# schema.net
KiCad netlist of a schematic drawn in EAGLE
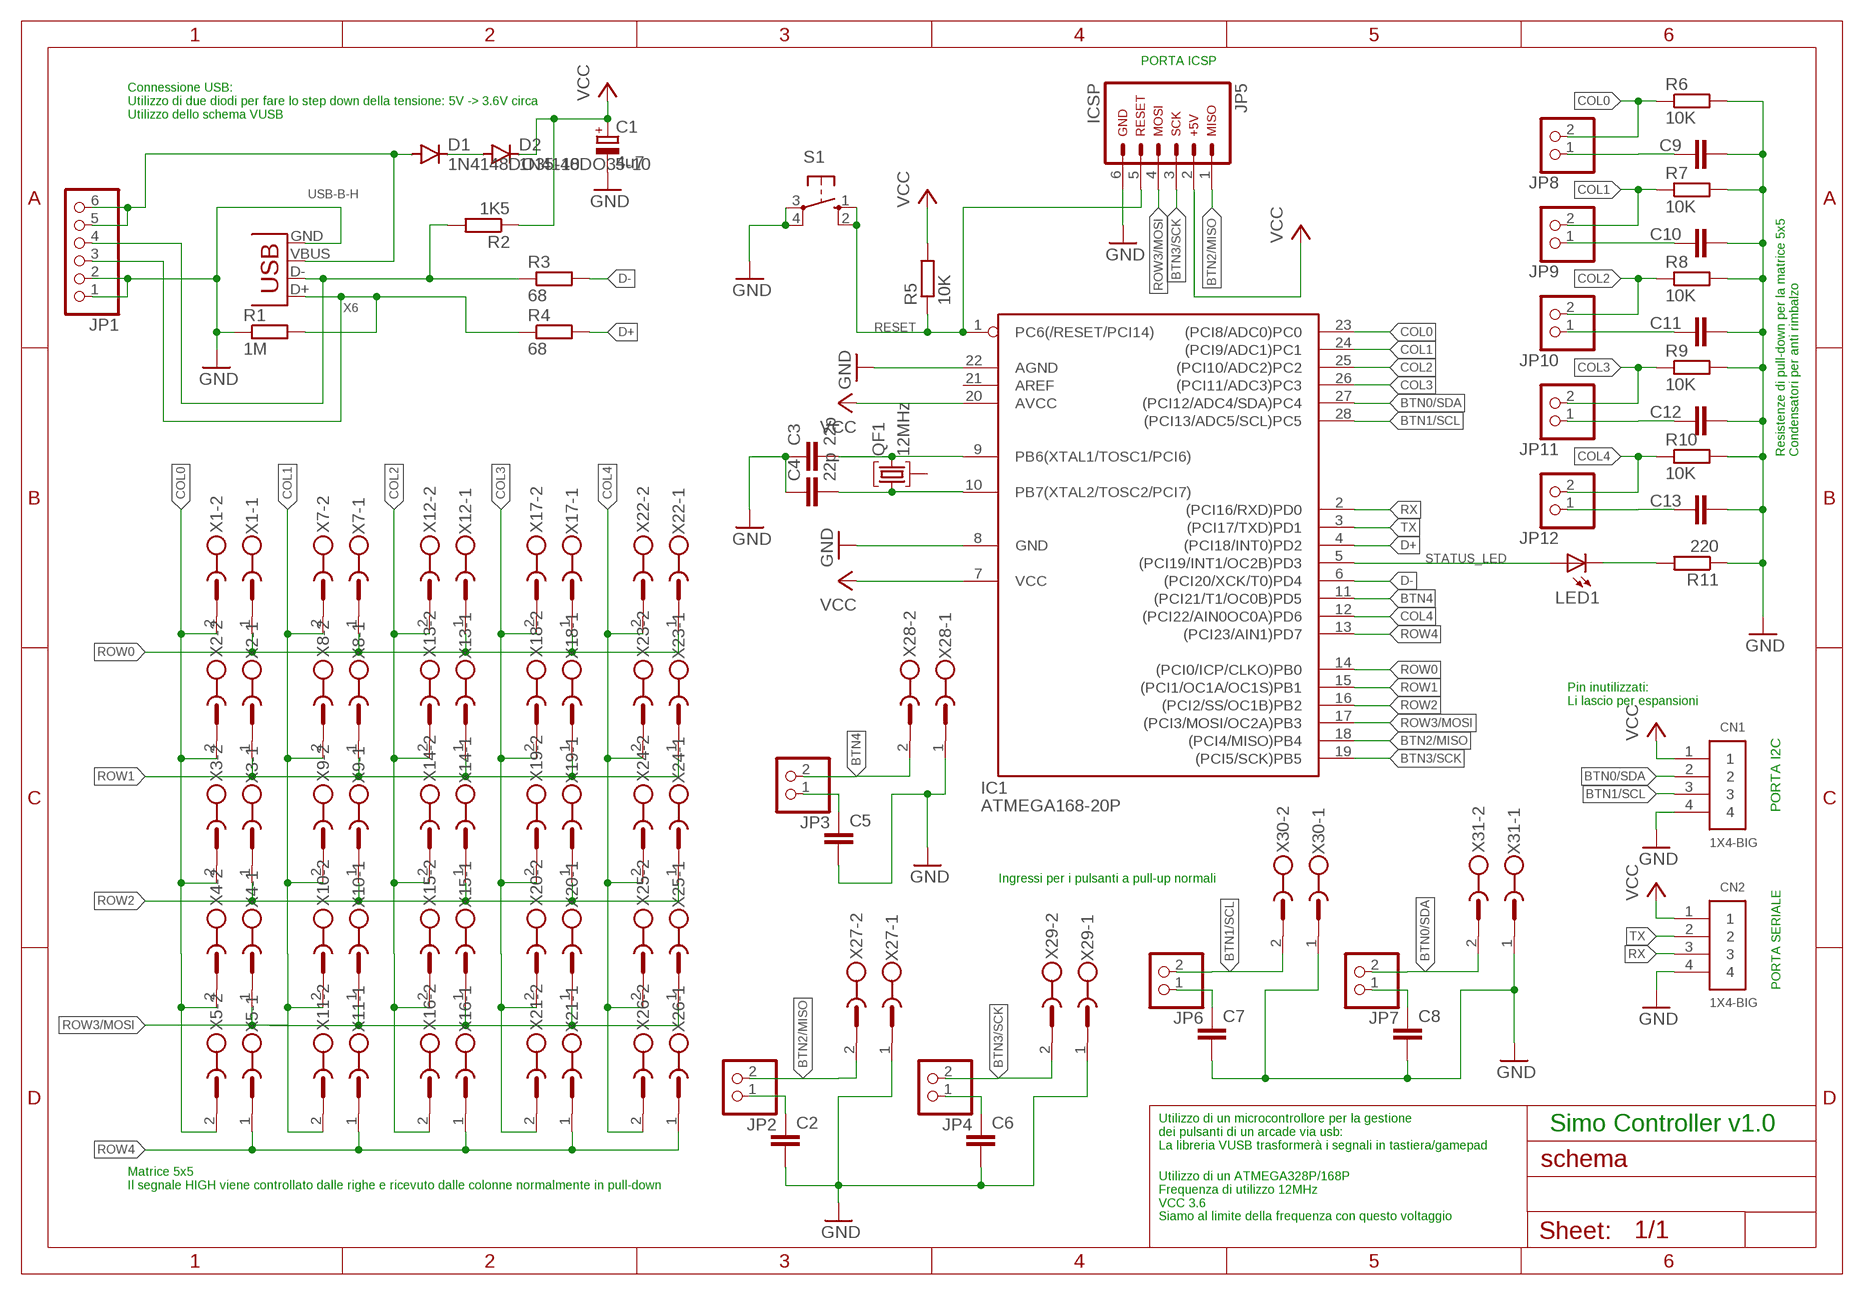
[diagram p0: schematic, sheet 1]

(export (version "E")
  (design (tool "Eeschema 10.0.6"))
  (components
    (comp (ref "C1")
      (value "4u7")
      (footprint "eagle-import:E5-6")
      (libsource (lib "eagle-import") (part "CPOL-EUE5-6"))
    )
    (comp (ref "C2")
      (value "C-EU050-024X044")
      (footprint "eagle-import:C050-024X044")
      (libsource (lib "eagle-import") (part "C-EU050-024X044"))
    )
    (comp (ref "C3")
      (value "22p")
      (footprint "eagle-import:C025-030X050")
      (libsource (lib "eagle-import") (part "C-EU025-030X050"))
    )
    (comp (ref "C4")
      (value "22p")
      (footprint "eagle-import:C025-030X050")
      (libsource (lib "eagle-import") (part "C-EU025-030X050"))
    )
    (comp (ref "C5")
      (value "C-EU050-024X044")
      (footprint "eagle-import:C050-024X044")
      (libsource (lib "eagle-import") (part "C-EU050-024X044"))
    )
    (comp (ref "C6")
      (value "C-EU050-024X044")
      (footprint "eagle-import:C050-024X044")
      (libsource (lib "eagle-import") (part "C-EU050-024X044"))
    )
    (comp (ref "C7")
      (value "C-EU050-024X044")
      (footprint "eagle-import:C050-024X044")
      (libsource (lib "eagle-import") (part "C-EU050-024X044"))
    )
    (comp (ref "C8")
      (value "C-EU050-024X044")
      (footprint "eagle-import:C050-024X044")
      (libsource (lib "eagle-import") (part "C-EU050-024X044"))
    )
    (comp (ref "C9")
      (value "C-EU050-024X044")
      (footprint "eagle-import:C050-024X044")
      (libsource (lib "eagle-import") (part "C-EU050-024X044"))
    )
    (comp (ref "C10")
      (value "C-EU050-024X044")
      (footprint "eagle-import:C050-024X044")
      (libsource (lib "eagle-import") (part "C-EU050-024X044"))
    )
    (comp (ref "C11")
      (value "C-EU050-024X044")
      (footprint "eagle-import:C050-024X044")
      (libsource (lib "eagle-import") (part "C-EU050-024X044"))
    )
    (comp (ref "C12")
      (value "C-EU050-024X044")
      (footprint "eagle-import:C050-024X044")
      (libsource (lib "eagle-import") (part "C-EU050-024X044"))
    )
    (comp (ref "C13")
      (value "C-EU050-024X044")
      (footprint "eagle-import:C050-024X044")
      (libsource (lib "eagle-import") (part "C-EU050-024X044"))
    )
    (comp (ref "CN1")
      (value "1X4-BIG")
      (footprint "eagle-import:1X04-BIG")
      (libsource (lib "eagle-import") (part "1X4-BIG"))
    )
    (comp (ref "CN2")
      (value "1X4-BIG")
      (footprint "eagle-import:1X04-BIG")
      (libsource (lib "eagle-import") (part "1X4-BIG"))
    )
    (comp (ref "D1")
      (value "1N4148DO35-10")
      (footprint "eagle-import:DO35-10")
      (libsource (lib "eagle-import") (part "1N4148DO35-10"))
    )
    (comp (ref "D2")
      (value "1N4148DO35-10")
      (footprint "eagle-import:DO35-10")
      (libsource (lib "eagle-import") (part "1N4148DO35-10"))
    )
    (comp (ref "IC1")
      (value "ATMEGA168-20P")
      (footprint "eagle-import:DIL28-3")
      (libsource (lib "eagle-import") (part "ATMEGA168P-20"))
    )
    (comp (ref "JP1")
      (value "PINHD-1X6")
      (footprint "eagle-import:1X06")
      (libsource (lib "eagle-import") (part "PINHD-1X6"))
    )
    (comp (ref "JP2")
      (value "PINHD-1X2")
      (footprint "eagle-import:1X02")
      (libsource (lib "eagle-import") (part "PINHD-1X2"))
    )
    (comp (ref "JP3")
      (value "PINHD-1X2")
      (footprint "eagle-import:1X02")
      (libsource (lib "eagle-import") (part "PINHD-1X2"))
    )
    (comp (ref "JP4")
      (value "PINHD-1X2")
      (footprint "eagle-import:1X02")
      (libsource (lib "eagle-import") (part "PINHD-1X2"))
    )
    (comp (ref "JP5")
      (value "ARDUINO_CONN-ICSP")
      (footprint "eagle-import:CONN-2X03")
      (libsource (lib "eagle-import") (part "ARDUINO_CONN-ICSP"))
    )
    (comp (ref "JP6")
      (value "PINHD-1X2")
      (footprint "eagle-import:1X02")
      (libsource (lib "eagle-import") (part "PINHD-1X2"))
    )
    (comp (ref "JP7")
      (value "PINHD-1X2")
      (footprint "eagle-import:1X02")
      (libsource (lib "eagle-import") (part "PINHD-1X2"))
    )
    (comp (ref "JP8")
      (value "PINHD-1X2")
      (footprint "eagle-import:1X02")
      (libsource (lib "eagle-import") (part "PINHD-1X2"))
    )
    (comp (ref "JP9")
      (value "PINHD-1X2")
      (footprint "eagle-import:1X02")
      (libsource (lib "eagle-import") (part "PINHD-1X2"))
    )
    (comp (ref "JP10")
      (value "PINHD-1X2")
      (footprint "eagle-import:1X02")
      (libsource (lib "eagle-import") (part "PINHD-1X2"))
    )
    (comp (ref "JP11")
      (value "PINHD-1X2")
      (footprint "eagle-import:1X02")
      (libsource (lib "eagle-import") (part "PINHD-1X2"))
    )
    (comp (ref "JP12")
      (value "PINHD-1X2")
      (footprint "eagle-import:1X02")
      (libsource (lib "eagle-import") (part "PINHD-1X2"))
    )
    (comp (ref "LED1")
      (value "LED3MM")
      (footprint "eagle-import:LED3MM")
      (libsource (lib "eagle-import") (part "LED3MM"))
    )
    (comp (ref "QF1")
      (value "12MHz")
      (footprint "eagle-import:HC49U")
      (libsource (lib "eagle-import") (part "10G7A-12.5KHZ"))
    )
    (comp (ref "R1")
      (value "1M")
      (footprint "eagle-import:0309_12")
      (libsource (lib "eagle-import") (part "R-EU_0309/12"))
    )
    (comp (ref "R2")
      (value "1K5")
      (footprint "eagle-import:0309_12")
      (libsource (lib "eagle-import") (part "R-EU_0309/12"))
    )
    (comp (ref "R3")
      (value "68")
      (footprint "eagle-import:0309_12")
      (libsource (lib "eagle-import") (part "R-EU_0309/12"))
    )
    (comp (ref "R4")
      (value "68")
      (footprint "eagle-import:0309_12")
      (libsource (lib "eagle-import") (part "R-EU_0309/12"))
    )
    (comp (ref "R5")
      (value "10K")
      (footprint "eagle-import:0309_12")
      (libsource (lib "eagle-import") (part "R-EU_0309/12"))
    )
    (comp (ref "R6")
      (value "10K")
      (footprint "eagle-import:0309_12")
      (libsource (lib "eagle-import") (part "R-EU_0309/12"))
    )
    (comp (ref "R7")
      (value "10K")
      (footprint "eagle-import:0309_12")
      (libsource (lib "eagle-import") (part "R-EU_0309/12"))
    )
    (comp (ref "R8")
      (value "10K")
      (footprint "eagle-import:0309_12")
      (libsource (lib "eagle-import") (part "R-EU_0309/12"))
    )
    (comp (ref "R9")
      (value "10K")
      (footprint "eagle-import:0309_12")
      (libsource (lib "eagle-import") (part "R-EU_0309/12"))
    )
    (comp (ref "R10")
      (value "10K")
      (footprint "eagle-import:0309_12")
      (libsource (lib "eagle-import") (part "R-EU_0309/12"))
    )
    (comp (ref "R11")
      (value "220")
      (footprint "eagle-import:0204_7")
      (libsource (lib "eagle-import") (part "R-EU_0204/7"))
    )
    (comp (ref "S1")
      (value "10-XX")
      (footprint "eagle-import:B3F-10XX")
      (fields (field (name "MPN") "B3F-1000"))
      (libsource (lib "eagle-import") (part "10-XX"))
    )
    (comp (ref "X1")
      (value "MSTBV2")
      (footprint "eagle-import:MSTBV2")
      (libsource (lib "eagle-import") (part "MSTBV2"))
    )
    (comp (ref "X2")
      (value "MSTBV2")
      (footprint "eagle-import:MSTBV2")
      (libsource (lib "eagle-import") (part "MSTBV2"))
    )
    (comp (ref "X3")
      (value "MSTBV2")
      (footprint "eagle-import:MSTBV2")
      (libsource (lib "eagle-import") (part "MSTBV2"))
    )
    (comp (ref "X4")
      (value "MSTBV2")
      (footprint "eagle-import:MSTBV2")
      (libsource (lib "eagle-import") (part "MSTBV2"))
    )
    (comp (ref "X5")
      (value "MSTBV2")
      (footprint "eagle-import:MSTBV2")
      (libsource (lib "eagle-import") (part "MSTBV2"))
    )
    (comp (ref "X6")
      (value "USB-B-H")
      (footprint "eagle-import:USB-B-H")
      (libsource (lib "eagle-import") (part "USB-B-H"))
    )
    (comp (ref "X7")
      (value "MSTBV2")
      (footprint "eagle-import:MSTBV2")
      (libsource (lib "eagle-import") (part "MSTBV2"))
    )
    (comp (ref "X8")
      (value "MSTBV2")
      (footprint "eagle-import:MSTBV2")
      (libsource (lib "eagle-import") (part "MSTBV2"))
    )
    (comp (ref "X9")
      (value "MSTBV2")
      (footprint "eagle-import:MSTBV2")
      (libsource (lib "eagle-import") (part "MSTBV2"))
    )
    (comp (ref "X10")
      (value "MSTBV2")
      (footprint "eagle-import:MSTBV2")
      (libsource (lib "eagle-import") (part "MSTBV2"))
    )
    (comp (ref "X11")
      (value "MSTBV2")
      (footprint "eagle-import:MSTBV2")
      (libsource (lib "eagle-import") (part "MSTBV2"))
    )
    (comp (ref "X12")
      (value "MSTBV2")
      (footprint "eagle-import:MSTBV2")
      (libsource (lib "eagle-import") (part "MSTBV2"))
    )
    (comp (ref "X13")
      (value "MSTBV2")
      (footprint "eagle-import:MSTBV2")
      (libsource (lib "eagle-import") (part "MSTBV2"))
    )
    (comp (ref "X14")
      (value "MSTBV2")
      (footprint "eagle-import:MSTBV2")
      (libsource (lib "eagle-import") (part "MSTBV2"))
    )
    (comp (ref "X15")
      (value "MSTBV2")
      (footprint "eagle-import:MSTBV2")
      (libsource (lib "eagle-import") (part "MSTBV2"))
    )
    (comp (ref "X16")
      (value "MSTBV2")
      (footprint "eagle-import:MSTBV2")
      (libsource (lib "eagle-import") (part "MSTBV2"))
    )
    (comp (ref "X17")
      (value "MSTBV2")
      (footprint "eagle-import:MSTBV2")
      (libsource (lib "eagle-import") (part "MSTBV2"))
    )
    (comp (ref "X18")
      (value "MSTBV2")
      (footprint "eagle-import:MSTBV2")
      (libsource (lib "eagle-import") (part "MSTBV2"))
    )
    (comp (ref "X19")
      (value "MSTBV2")
      (footprint "eagle-import:MSTBV2")
      (libsource (lib "eagle-import") (part "MSTBV2"))
    )
    (comp (ref "X20")
      (value "MSTBV2")
      (footprint "eagle-import:MSTBV2")
      (libsource (lib "eagle-import") (part "MSTBV2"))
    )
    (comp (ref "X21")
      (value "MSTBV2")
      (footprint "eagle-import:MSTBV2")
      (libsource (lib "eagle-import") (part "MSTBV2"))
    )
    (comp (ref "X22")
      (value "MSTBV2")
      (footprint "eagle-import:MSTBV2")
      (libsource (lib "eagle-import") (part "MSTBV2"))
    )
    (comp (ref "X23")
      (value "MSTBV2")
      (footprint "eagle-import:MSTBV2")
      (libsource (lib "eagle-import") (part "MSTBV2"))
    )
    (comp (ref "X24")
      (value "MSTBV2")
      (footprint "eagle-import:MSTBV2")
      (libsource (lib "eagle-import") (part "MSTBV2"))
    )
    (comp (ref "X25")
      (value "MSTBV2")
      (footprint "eagle-import:MSTBV2")
      (libsource (lib "eagle-import") (part "MSTBV2"))
    )
    (comp (ref "X26")
      (value "MSTBV2")
      (footprint "eagle-import:MSTBV2")
      (libsource (lib "eagle-import") (part "MSTBV2"))
    )
    (comp (ref "X27")
      (value "MSTBV2")
      (footprint "eagle-import:MSTBV2")
      (libsource (lib "eagle-import") (part "MSTBV2"))
    )
    (comp (ref "X28")
      (value "MSTBV2")
      (footprint "eagle-import:MSTBV2")
      (libsource (lib "eagle-import") (part "MSTBV2"))
    )
    (comp (ref "X29")
      (value "MSTBV2")
      (footprint "eagle-import:MSTBV2")
      (libsource (lib "eagle-import") (part "MSTBV2"))
    )
    (comp (ref "X30")
      (value "MSTBV2")
      (footprint "eagle-import:MSTBV2")
      (libsource (lib "eagle-import") (part "MSTBV2"))
    )
    (comp (ref "X31")
      (value "MSTBV2")
      (footprint "eagle-import:MSTBV2")
      (libsource (lib "eagle-import") (part "MSTBV2"))
    )
  )
  (nets
    (net (code "1") (name "/RESET") (class "Default")
      (node (ref "IC1") (pin "1") (pinfunction "PC6(/RESET/PCI14)_1") (pintype "bidirectional"))
      (node (ref "JP5") (pin "5") (pinfunction "5_5") (pintype "passive"))
      (node (ref "R5") (pin "1") (pinfunction "1_1") (pintype "passive"))
      (node (ref "S1") (pin "1") (pinfunction "S_1") (pintype "passive"))
      (node (ref "S1") (pin "2") (pinfunction "S1_2") (pintype "passive"))
    )
    (net (code "2") (name "/STATUS_LED") (class "Default")
      (node (ref "IC1") (pin "5") (pinfunction "(PCI19/INT1/OC2B)PD3_5") (pintype "bidirectional"))
      (node (ref "LED1") (pin "A") (pinfunction "A_A") (pintype "passive"))
    )
    (net (code "3") (name "BTN0{slash}SDA") (class "Default")
      (node (ref "CN1") (pin "2") (pinfunction "2_2") (pintype "bidirectional"))
      (node (ref "IC1") (pin "27") (pinfunction "(PCI12/ADC4/SDA)PC4_27") (pintype "bidirectional"))
      (node (ref "JP7") (pin "2") (pinfunction "2_2") (pintype "passive"))
      (node (ref "X31") (pin "2") (pinfunction "SK_2") (pintype "passive"))
    )
    (net (code "4") (name "BTN1{slash}SCL") (class "Default")
      (node (ref "CN1") (pin "3") (pinfunction "3_3") (pintype "bidirectional"))
      (node (ref "IC1") (pin "28") (pinfunction "(PCI13/ADC5/SCL)PC5_28") (pintype "bidirectional"))
      (node (ref "JP6") (pin "2") (pinfunction "2_2") (pintype "passive"))
      (node (ref "X30") (pin "2") (pinfunction "SK_2") (pintype "passive"))
    )
    (net (code "5") (name "BTN2{slash}MISO") (class "Default")
      (node (ref "IC1") (pin "18") (pinfunction "(PCI4/MISO)PB4_18") (pintype "bidirectional"))
      (node (ref "JP2") (pin "2") (pinfunction "2_2") (pintype "passive"))
      (node (ref "JP5") (pin "1") (pinfunction "1_1") (pintype "passive"))
      (node (ref "X27") (pin "2") (pinfunction "SK_2") (pintype "passive"))
    )
    (net (code "6") (name "BTN3{slash}SCK") (class "Default")
      (node (ref "IC1") (pin "19") (pinfunction "(PCI5/SCK)PB5_19") (pintype "bidirectional"))
      (node (ref "JP4") (pin "2") (pinfunction "2_2") (pintype "passive"))
      (node (ref "JP5") (pin "3") (pinfunction "3_3") (pintype "passive"))
      (node (ref "X29") (pin "2") (pinfunction "SK_2") (pintype "passive"))
    )
    (net (code "7") (name "BTN4") (class "Default")
      (node (ref "IC1") (pin "11") (pinfunction "(PCI21/T1/OC0B)PD5_11") (pintype "bidirectional"))
      (node (ref "JP3") (pin "2") (pinfunction "2_2") (pintype "passive"))
      (node (ref "X28") (pin "2") (pinfunction "SK_2") (pintype "passive"))
    )
    (net (code "8") (name "COL0") (class "Default")
      (node (ref "IC1") (pin "23") (pinfunction "(PCI8/ADC0)PC0_23") (pintype "bidirectional"))
      (node (ref "JP8") (pin "2") (pinfunction "2_2") (pintype "passive"))
      (node (ref "R6") (pin "1") (pinfunction "1_1") (pintype "passive"))
      (node (ref "X1") (pin "2") (pinfunction "SK_2") (pintype "passive"))
      (node (ref "X2") (pin "2") (pinfunction "SK_2") (pintype "passive"))
      (node (ref "X3") (pin "2") (pinfunction "SK_2") (pintype "passive"))
      (node (ref "X4") (pin "2") (pinfunction "SK_2") (pintype "passive"))
      (node (ref "X5") (pin "2") (pinfunction "SK_2") (pintype "passive"))
    )
    (net (code "9") (name "COL1") (class "Default")
      (node (ref "IC1") (pin "24") (pinfunction "(PCI9/ADC1)PC1_24") (pintype "bidirectional"))
      (node (ref "JP9") (pin "2") (pinfunction "2_2") (pintype "passive"))
      (node (ref "R7") (pin "1") (pinfunction "1_1") (pintype "passive"))
      (node (ref "X10") (pin "2") (pinfunction "SK_2") (pintype "passive"))
      (node (ref "X11") (pin "2") (pinfunction "SK_2") (pintype "passive"))
      (node (ref "X7") (pin "2") (pinfunction "SK_2") (pintype "passive"))
      (node (ref "X8") (pin "2") (pinfunction "SK_2") (pintype "passive"))
      (node (ref "X9") (pin "2") (pinfunction "SK_2") (pintype "passive"))
    )
    (net (code "10") (name "COL2") (class "Default")
      (node (ref "IC1") (pin "25") (pinfunction "(PCI10/ADC2)PC2_25") (pintype "bidirectional"))
      (node (ref "JP10") (pin "2") (pinfunction "2_2") (pintype "passive"))
      (node (ref "R8") (pin "1") (pinfunction "1_1") (pintype "passive"))
      (node (ref "X12") (pin "2") (pinfunction "SK_2") (pintype "passive"))
      (node (ref "X13") (pin "2") (pinfunction "SK_2") (pintype "passive"))
      (node (ref "X14") (pin "2") (pinfunction "SK_2") (pintype "passive"))
      (node (ref "X15") (pin "2") (pinfunction "SK_2") (pintype "passive"))
      (node (ref "X16") (pin "2") (pinfunction "SK_2") (pintype "passive"))
    )
    (net (code "11") (name "COL3") (class "Default")
      (node (ref "IC1") (pin "26") (pinfunction "(PCI11/ADC3)PC3_26") (pintype "bidirectional"))
      (node (ref "JP11") (pin "2") (pinfunction "2_2") (pintype "passive"))
      (node (ref "R9") (pin "1") (pinfunction "1_1") (pintype "passive"))
      (node (ref "X17") (pin "2") (pinfunction "SK_2") (pintype "passive"))
      (node (ref "X18") (pin "2") (pinfunction "SK_2") (pintype "passive"))
      (node (ref "X19") (pin "2") (pinfunction "SK_2") (pintype "passive"))
      (node (ref "X20") (pin "2") (pinfunction "SK_2") (pintype "passive"))
      (node (ref "X21") (pin "2") (pinfunction "SK_2") (pintype "passive"))
    )
    (net (code "12") (name "COL4") (class "Default")
      (node (ref "IC1") (pin "12") (pinfunction "(PCI22/AIN0OC0A)PD6_12") (pintype "bidirectional"))
      (node (ref "JP12") (pin "2") (pinfunction "2_2") (pintype "passive"))
      (node (ref "R10") (pin "1") (pinfunction "1_1") (pintype "passive"))
      (node (ref "X22") (pin "2") (pinfunction "SK_2") (pintype "passive"))
      (node (ref "X23") (pin "2") (pinfunction "SK_2") (pintype "passive"))
      (node (ref "X24") (pin "2") (pinfunction "SK_2") (pintype "passive"))
      (node (ref "X25") (pin "2") (pinfunction "SK_2") (pintype "passive"))
      (node (ref "X26") (pin "2") (pinfunction "SK_2") (pintype "passive"))
    )
    (net (code "13") (name "D+") (class "Default")
      (node (ref "IC1") (pin "4") (pinfunction "(PCI18/INT0)PD2_4") (pintype "bidirectional"))
      (node (ref "R4") (pin "2") (pinfunction "2_2") (pintype "passive"))
    )
    (net (code "14") (name "D-") (class "Default")
      (node (ref "IC1") (pin "6") (pinfunction "(PCI20/XCK/T0)PD4_6") (pintype "bidirectional"))
      (node (ref "R3") (pin "2") (pinfunction "2_2") (pintype "passive"))
    )
    (net (code "15") (name "GND") (class "Default")
      (node (ref "C1") (pin "-") (pinfunction "-_-") (pintype "passive"))
      (node (ref "C10") (pin "2") (pinfunction "2_2") (pintype "passive"))
      (node (ref "C11") (pin "2") (pinfunction "2_2") (pintype "passive"))
      (node (ref "C12") (pin "2") (pinfunction "2_2") (pintype "passive"))
      (node (ref "C13") (pin "2") (pinfunction "2_2") (pintype "passive"))
      (node (ref "C2") (pin "2") (pinfunction "2_2") (pintype "passive"))
      (node (ref "C3") (pin "1") (pinfunction "1_1") (pintype "passive"))
      (node (ref "C4") (pin "1") (pinfunction "1_1") (pintype "passive"))
      (node (ref "C5") (pin "2") (pinfunction "2_2") (pintype "passive"))
      (node (ref "C6") (pin "2") (pinfunction "2_2") (pintype "passive"))
      (node (ref "C7") (pin "2") (pinfunction "2_2") (pintype "passive"))
      (node (ref "C8") (pin "2") (pinfunction "2_2") (pintype "passive"))
      (node (ref "C9") (pin "2") (pinfunction "2_2") (pintype "passive"))
      (node (ref "CN1") (pin "4") (pinfunction "4_4") (pintype "bidirectional"))
      (node (ref "CN2") (pin "4") (pinfunction "4_4") (pintype "bidirectional"))
      (node (ref "IC1") (pin "22") (pinfunction "AGND_22") (pintype "bidirectional"))
      (node (ref "IC1") (pin "8") (pinfunction "GND_8") (pintype "bidirectional"))
      (node (ref "JP1") (pin "1") (pinfunction "1_1") (pintype "passive"))
      (node (ref "JP1") (pin "2") (pinfunction "2_2") (pintype "passive"))
      (node (ref "JP5") (pin "6") (pinfunction "6_6") (pintype "passive"))
      (node (ref "R1") (pin "1") (pinfunction "1_1") (pintype "passive"))
      (node (ref "R10") (pin "2") (pinfunction "2_2") (pintype "passive"))
      (node (ref "R11") (pin "1") (pinfunction "1_1") (pintype "passive"))
      (node (ref "R6") (pin "2") (pinfunction "2_2") (pintype "passive"))
      (node (ref "R7") (pin "2") (pinfunction "2_2") (pintype "passive"))
      (node (ref "R8") (pin "2") (pinfunction "2_2") (pintype "passive"))
      (node (ref "R9") (pin "2") (pinfunction "2_2") (pintype "passive"))
      (node (ref "S1") (pin "3") (pinfunction "P_3") (pintype "passive"))
      (node (ref "S1") (pin "4") (pinfunction "P1_4") (pintype "passive"))
      (node (ref "X27") (pin "1") (pinfunction "SK_1") (pintype "passive"))
      (node (ref "X28") (pin "1") (pinfunction "SK_1") (pintype "passive"))
      (node (ref "X29") (pin "1") (pinfunction "SK_1") (pintype "passive"))
      (node (ref "X30") (pin "1") (pinfunction "SK_1") (pintype "passive"))
      (node (ref "X31") (pin "1") (pinfunction "SK_1") (pintype "passive"))
      (node (ref "X6") (pin "GND") (pinfunction "GND_GND") (pintype "bidirectional"))
    )
    (net (code "16") (name "Net-(C2-Pad1)") (class "Default")
      (node (ref "C2") (pin "1") (pinfunction "1_1") (pintype "passive"))
      (node (ref "JP2") (pin "1") (pinfunction "1_1") (pintype "passive"))
    )
    (net (code "17") (name "Net-(C5-Pad1)") (class "Default")
      (node (ref "C5") (pin "1") (pinfunction "1_1") (pintype "passive"))
      (node (ref "JP3") (pin "1") (pinfunction "1_1") (pintype "passive"))
    )
    (net (code "18") (name "Net-(C6-Pad1)") (class "Default")
      (node (ref "C6") (pin "1") (pinfunction "1_1") (pintype "passive"))
      (node (ref "JP4") (pin "1") (pinfunction "1_1") (pintype "passive"))
    )
    (net (code "19") (name "Net-(C7-Pad1)") (class "Default")
      (node (ref "C7") (pin "1") (pinfunction "1_1") (pintype "passive"))
      (node (ref "JP6") (pin "1") (pinfunction "1_1") (pintype "passive"))
    )
    (net (code "20") (name "Net-(C8-Pad1)") (class "Default")
      (node (ref "C8") (pin "1") (pinfunction "1_1") (pintype "passive"))
      (node (ref "JP7") (pin "1") (pinfunction "1_1") (pintype "passive"))
    )
    (net (code "21") (name "Net-(C9-Pad1)") (class "Default")
      (node (ref "C9") (pin "1") (pinfunction "1_1") (pintype "passive"))
      (node (ref "JP8") (pin "1") (pinfunction "1_1") (pintype "passive"))
    )
    (net (code "22") (name "Net-(C10-Pad1)") (class "Default")
      (node (ref "C10") (pin "1") (pinfunction "1_1") (pintype "passive"))
      (node (ref "JP9") (pin "1") (pinfunction "1_1") (pintype "passive"))
    )
    (net (code "23") (name "Net-(C11-Pad1)") (class "Default")
      (node (ref "C11") (pin "1") (pinfunction "1_1") (pintype "passive"))
      (node (ref "JP10") (pin "1") (pinfunction "1_1") (pintype "passive"))
    )
    (net (code "24") (name "Net-(C12-Pad1)") (class "Default")
      (node (ref "C12") (pin "1") (pinfunction "1_1") (pintype "passive"))
      (node (ref "JP11") (pin "1") (pinfunction "1_1") (pintype "passive"))
    )
    (net (code "25") (name "Net-(C13-Pad1)") (class "Default")
      (node (ref "C13") (pin "1") (pinfunction "1_1") (pintype "passive"))
      (node (ref "JP12") (pin "1") (pinfunction "1_1") (pintype "passive"))
    )
    (net (code "26") (name "Net-(D1-PadA)") (class "Default")
      (node (ref "D1") (pin "A") (pinfunction "A_A") (pintype "passive"))
      (node (ref "JP1") (pin "5") (pinfunction "5_5") (pintype "passive"))
      (node (ref "JP1") (pin "6") (pinfunction "6_6") (pintype "passive"))
      (node (ref "X6") (pin "VBUS") (pinfunction "VBUS_VBUS") (pintype "bidirectional"))
    )
    (net (code "27") (name "Net-(D1-PadC)") (class "Default")
      (node (ref "D1") (pin "C") (pinfunction "C_C") (pintype "passive"))
      (node (ref "D2") (pin "A") (pinfunction "A_A") (pintype "passive"))
    )
    (net (code "28") (name "Net-(IC1-PB6(XTAL1{slash}TOSC1{slash}PCI6))") (class "Default")
      (node (ref "C3") (pin "2") (pinfunction "2_2") (pintype "passive"))
      (node (ref "IC1") (pin "9") (pinfunction "PB6(XTAL1/TOSC1/PCI6)_9") (pintype "bidirectional"))
      (node (ref "QF1") (pin "3") (pinfunction "3_3") (pintype "passive"))
    )
    (net (code "29") (name "Net-(IC1-PB7(XTAL2{slash}TOSC2{slash}PCI7))") (class "Default")
      (node (ref "C4") (pin "2") (pinfunction "2_2") (pintype "passive"))
      (node (ref "IC1") (pin "10") (pinfunction "PB7(XTAL2/TOSC2/PCI7)_10") (pintype "bidirectional"))
      (node (ref "QF1") (pin "1") (pinfunction "1_1") (pintype "passive"))
    )
    (net (code "30") (name "Net-(JP1-Pad3)") (class "Default")
      (node (ref "JP1") (pin "3") (pinfunction "3_3") (pintype "passive"))
      (node (ref "R1") (pin "2") (pinfunction "2_2") (pintype "passive"))
      (node (ref "R4") (pin "1") (pinfunction "1_1") (pintype "passive"))
      (node (ref "X6") (pin "D+") (pinfunction "D+_D+") (pintype "bidirectional"))
    )
    (net (code "31") (name "Net-(JP1-Pad4)") (class "Default")
      (node (ref "JP1") (pin "4") (pinfunction "4_4") (pintype "passive"))
      (node (ref "R2") (pin "2") (pinfunction "2_2") (pintype "passive"))
      (node (ref "R3") (pin "1") (pinfunction "1_1") (pintype "passive"))
      (node (ref "X6") (pin "D-") (pinfunction "D-_D-") (pintype "bidirectional"))
    )
    (net (code "32") (name "Net-(LED1-C)") (class "Default")
      (node (ref "LED1") (pin "K") (pinfunction "C_K") (pintype "passive"))
      (node (ref "R11") (pin "2") (pinfunction "2_2") (pintype "passive"))
    )
    (net (code "33") (name "ROW0") (class "Default")
      (node (ref "IC1") (pin "14") (pinfunction "(PCI0/ICP/CLKO)PB0_14") (pintype "bidirectional"))
      (node (ref "X1") (pin "1") (pinfunction "SK_1") (pintype "passive"))
      (node (ref "X12") (pin "1") (pinfunction "SK_1") (pintype "passive"))
      (node (ref "X17") (pin "1") (pinfunction "SK_1") (pintype "passive"))
      (node (ref "X22") (pin "1") (pinfunction "SK_1") (pintype "passive"))
      (node (ref "X7") (pin "1") (pinfunction "SK_1") (pintype "passive"))
    )
    (net (code "34") (name "ROW1") (class "Default")
      (node (ref "IC1") (pin "15") (pinfunction "(PCI1/OC1A/OC1S)PB1_15") (pintype "bidirectional"))
      (node (ref "X13") (pin "1") (pinfunction "SK_1") (pintype "passive"))
      (node (ref "X18") (pin "1") (pinfunction "SK_1") (pintype "passive"))
      (node (ref "X2") (pin "1") (pinfunction "SK_1") (pintype "passive"))
      (node (ref "X23") (pin "1") (pinfunction "SK_1") (pintype "passive"))
      (node (ref "X8") (pin "1") (pinfunction "SK_1") (pintype "passive"))
    )
    (net (code "35") (name "ROW2") (class "Default")
      (node (ref "IC1") (pin "16") (pinfunction "(PCI2/SS/OC1B)PB2_16") (pintype "bidirectional"))
      (node (ref "X14") (pin "1") (pinfunction "SK_1") (pintype "passive"))
      (node (ref "X19") (pin "1") (pinfunction "SK_1") (pintype "passive"))
      (node (ref "X24") (pin "1") (pinfunction "SK_1") (pintype "passive"))
      (node (ref "X3") (pin "1") (pinfunction "SK_1") (pintype "passive"))
      (node (ref "X9") (pin "1") (pinfunction "SK_1") (pintype "passive"))
    )
    (net (code "36") (name "ROW3{slash}MOSI") (class "Default")
      (node (ref "IC1") (pin "17") (pinfunction "(PCI3/MOSI/OC2A)PB3_17") (pintype "bidirectional"))
      (node (ref "JP5") (pin "4") (pinfunction "4_4") (pintype "passive"))
      (node (ref "X10") (pin "1") (pinfunction "SK_1") (pintype "passive"))
      (node (ref "X15") (pin "1") (pinfunction "SK_1") (pintype "passive"))
      (node (ref "X20") (pin "1") (pinfunction "SK_1") (pintype "passive"))
      (node (ref "X25") (pin "1") (pinfunction "SK_1") (pintype "passive"))
      (node (ref "X4") (pin "1") (pinfunction "SK_1") (pintype "passive"))
    )
    (net (code "37") (name "ROW4") (class "Default")
      (node (ref "IC1") (pin "13") (pinfunction "(PCI23/AIN1)PD7_13") (pintype "bidirectional"))
      (node (ref "X11") (pin "1") (pinfunction "SK_1") (pintype "passive"))
      (node (ref "X16") (pin "1") (pinfunction "SK_1") (pintype "passive"))
      (node (ref "X21") (pin "1") (pinfunction "SK_1") (pintype "passive"))
      (node (ref "X26") (pin "1") (pinfunction "SK_1") (pintype "passive"))
      (node (ref "X5") (pin "1") (pinfunction "SK_1") (pintype "passive"))
    )
    (net (code "38") (name "RX") (class "Default")
      (node (ref "CN2") (pin "3") (pinfunction "3_3") (pintype "bidirectional"))
      (node (ref "IC1") (pin "2") (pinfunction "(PCI16/RXD)PD0_2") (pintype "bidirectional"))
    )
    (net (code "39") (name "TX") (class "Default")
      (node (ref "CN2") (pin "2") (pinfunction "2_2") (pintype "bidirectional"))
      (node (ref "IC1") (pin "3") (pinfunction "(PCI17/TXD)PD1_3") (pintype "bidirectional"))
    )
    (net (code "40") (name "VCC") (class "Default")
      (node (ref "C1") (pin "+") (pinfunction "+_+") (pintype "passive"))
      (node (ref "CN1") (pin "1") (pinfunction "1_1") (pintype "bidirectional"))
      (node (ref "CN2") (pin "1") (pinfunction "1_1") (pintype "bidirectional"))
      (node (ref "D2") (pin "C") (pinfunction "C_C") (pintype "passive"))
      (node (ref "IC1") (pin "20") (pinfunction "AVCC_20") (pintype "bidirectional"))
      (node (ref "IC1") (pin "7") (pinfunction "VCC_7") (pintype "bidirectional"))
      (node (ref "JP5") (pin "2") (pinfunction "2_2") (pintype "passive"))
      (node (ref "R2") (pin "1") (pinfunction "1_1") (pintype "passive"))
      (node (ref "R5") (pin "2") (pinfunction "2_2") (pintype "passive"))
    )
    (net (code "41") (name "unconnected-(IC1-AREF-Pad21)") (class "Default")
      (node (ref "IC1") (pin "21") (pinfunction "AREF_21") (pintype "bidirectional"))
    )
    (net (code "42") (name "unconnected-(QF1-Pad2)") (class "Default")
      (node (ref "QF1") (pin "2") (pinfunction "2_2") (pintype "passive"))
    )
  )
)
